# 01_-_Edge-connections.net
KiCad netlist of a schematic drawn in Altium Designer
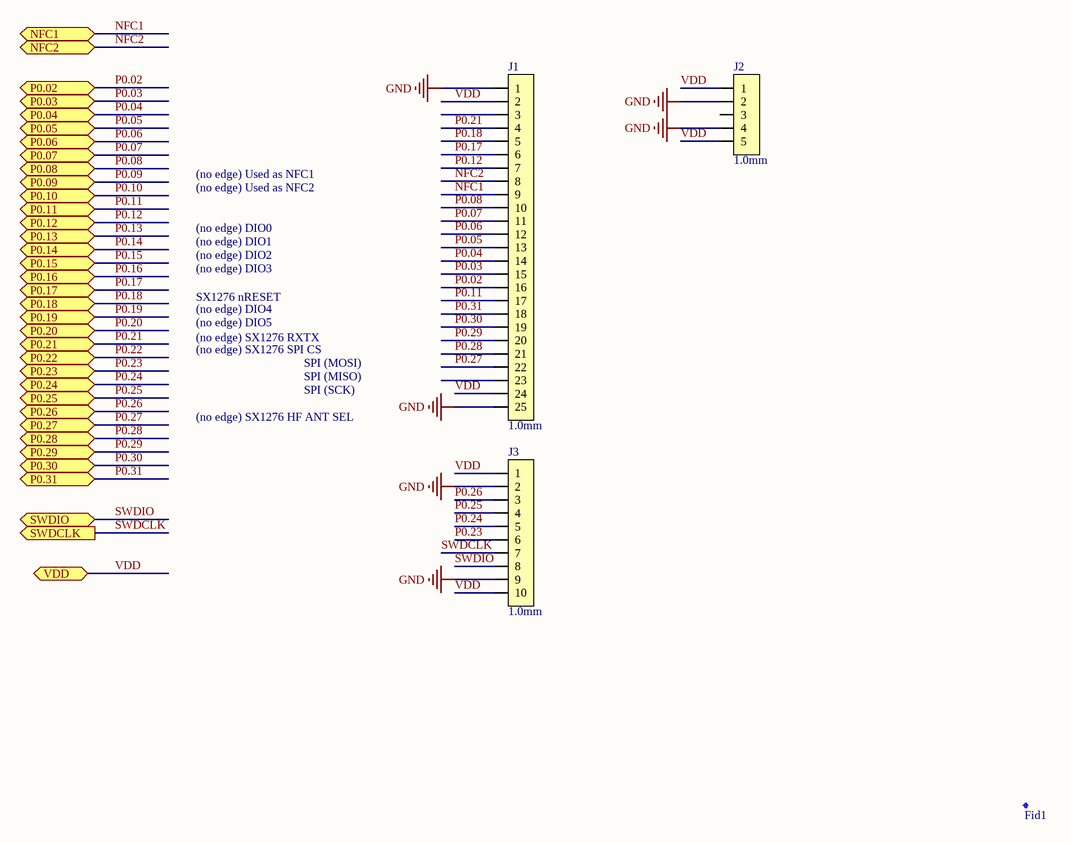
[diagram p0: [01] - Edge-connections.SchDoc]

(export (version "E")
  (design (tool "Eeschema 10.0.6"))
  (components
    (comp (ref "Fid1")
      (value "Fiducial mark")
      (footprint "Fiducial")
      (description "Fiducial Mark")
      (fields (field (name "PART NUMBER") "Fid-Mark") (field (name "PUBLISHER") "Nordic Semiconductor"))
      (libsource (lib "Skunkworks Library") (part "Fiducial"))
    )
    (comp (ref "J1")
      (value "1.0mm")
      (footprint "EDGE_MULTI_25")
      (description "Edge Connector, 25 pins, 1mm pitch")
      (libsource (lib "Skunkworks Library") (part "EDGE_MULTI_25_P_1mm"))
    )
    (comp (ref "J2")
      (value "1.0mm")
      (footprint "EDGE_MULTI_5")
      (description "Edge Connector, 5 pins, 1mm pitch")
      (libsource (lib "Skunkworks Library") (part "EDGE_MULTI_5_P_1mm"))
    )
    (comp (ref "J3")
      (value "1.0mm")
      (footprint "EDGE_MULTI_10")
      (description "Edge Connector, 10 pins, 1mm pitch")
      (libsource (lib "Skunkworks Library") (part "EDGE_MULTI_10_P_1mm"))
    )
    (comp (ref "LOGO1")
      (value "TELENOR_LOGO")
      (footprint "TELENOR_4mmx3.8mm")
      (libsource (lib "Skunkworks Library") (part "TELENOR_LOGO"))
    )
  )
  (nets
    (net (code "1") (name "/NFC1") (class "Default")
      (node (ref "J1") (pin "9") (pinfunction "9_9") (pintype "passive"))
    )
    (net (code "2") (name "/NFC2") (class "Default")
      (node (ref "J1") (pin "8") (pinfunction "8_8") (pintype "passive"))
    )
    (net (code "3") (name "/P0.02") (class "Default")
      (node (ref "J1") (pin "16") (pinfunction "16_16") (pintype "passive"))
    )
    (net (code "4") (name "/P0.03") (class "Default")
      (node (ref "J1") (pin "15") (pinfunction "15_15") (pintype "passive"))
    )
    (net (code "5") (name "/P0.04") (class "Default")
      (node (ref "J1") (pin "14") (pinfunction "14_14") (pintype "passive"))
    )
    (net (code "6") (name "/P0.05") (class "Default")
      (node (ref "J1") (pin "13") (pinfunction "13_13") (pintype "passive"))
    )
    (net (code "7") (name "/P0.06") (class "Default")
      (node (ref "J1") (pin "12") (pinfunction "12_12") (pintype "passive"))
    )
    (net (code "8") (name "/P0.07") (class "Default")
      (node (ref "J1") (pin "11") (pinfunction "11_11") (pintype "passive"))
    )
    (net (code "9") (name "/P0.08") (class "Default")
      (node (ref "J1") (pin "10") (pinfunction "10_10") (pintype "passive"))
    )
    (net (code "12") (name "/P0.11") (class "Default")
      (node (ref "J1") (pin "17") (pinfunction "17_17") (pintype "passive"))
    )
    (net (code "13") (name "/P0.12") (class "Default")
      (node (ref "J1") (pin "7") (pinfunction "7_7") (pintype "passive"))
    )
    (net (code "18") (name "/P0.17") (class "Default")
      (node (ref "J1") (pin "6") (pinfunction "6_6") (pintype "passive"))
    )
    (net (code "19") (name "/P0.18") (class "Default")
      (node (ref "J1") (pin "5") (pinfunction "5_5") (pintype "passive"))
    )
    (net (code "22") (name "/P0.21") (class "Default")
      (node (ref "J1") (pin "4") (pinfunction "4_4") (pintype "passive"))
    )
    (net (code "24") (name "/P0.23") (class "Default")
      (node (ref "J3") (pin "6") (pinfunction "6_6") (pintype "passive"))
    )
    (net (code "25") (name "/P0.24") (class "Default")
      (node (ref "J3") (pin "5") (pinfunction "5_5") (pintype "passive"))
    )
    (net (code "26") (name "/P0.25") (class "Default")
      (node (ref "J3") (pin "4") (pinfunction "4_4") (pintype "passive"))
    )
    (net (code "27") (name "/P0.26") (class "Default")
      (node (ref "J3") (pin "3") (pinfunction "3_3") (pintype "passive"))
    )
    (net (code "28") (name "/P0.27") (class "Default")
      (node (ref "J1") (pin "22") (pinfunction "22_22") (pintype "passive"))
    )
    (net (code "29") (name "/P0.28") (class "Default")
      (node (ref "J1") (pin "21") (pinfunction "21_21") (pintype "passive"))
    )
    (net (code "30") (name "/P0.29") (class "Default")
      (node (ref "J1") (pin "20") (pinfunction "20_20") (pintype "passive"))
    )
    (net (code "31") (name "/P0.30") (class "Default")
      (node (ref "J1") (pin "19") (pinfunction "19_19") (pintype "passive"))
    )
    (net (code "32") (name "/P0.31") (class "Default")
      (node (ref "J1") (pin "18") (pinfunction "18_18") (pintype "passive"))
    )
    (net (code "33") (name "/SWDCLK") (class "Default")
      (node (ref "J3") (pin "7") (pinfunction "7_7") (pintype "passive"))
    )
    (net (code "34") (name "/SWDIO") (class "Default")
      (node (ref "J3") (pin "8") (pinfunction "8_8") (pintype "passive"))
    )
    (net (code "35") (name "/VDD") (class "Default")
      (node (ref "J1") (pin "2") (pinfunction "2_2") (pintype "passive"))
      (node (ref "J1") (pin "24") (pinfunction "24_24") (pintype "passive"))
      (node (ref "J2") (pin "1") (pinfunction "1_1") (pintype "passive"))
      (node (ref "J2") (pin "5") (pinfunction "5_5") (pintype "passive"))
      (node (ref "J3") (pin "1") (pinfunction "1_1") (pintype "passive"))
      (node (ref "J3") (pin "10") (pinfunction "10_10") (pintype "passive"))
    )
    (net (code "36") (name "GND") (class "Default")
      (node (ref "J1") (pin "1") (pinfunction "1_1") (pintype "passive"))
      (node (ref "J1") (pin "25") (pinfunction "25_25") (pintype "passive"))
      (node (ref "J2") (pin "2") (pinfunction "2_2") (pintype "passive"))
      (node (ref "J2") (pin "4") (pinfunction "4_4") (pintype "passive"))
      (node (ref "J3") (pin "2") (pinfunction "2_2") (pintype "passive"))
      (node (ref "J3") (pin "9") (pinfunction "9_9") (pintype "passive"))
    )
    (net (code "37") (name "unconnected-(J1-Pad3)") (class "Default")
      (node (ref "J1") (pin "3") (pinfunction "3_3") (pintype "passive"))
    )
    (net (code "38") (name "unconnected-(J1-Pad23)") (class "Default")
      (node (ref "J1") (pin "23") (pinfunction "23_23") (pintype "passive"))
    )
    (net (code "39") (name "unconnected-(J2-Pad3)") (class "Default")
      (node (ref "J2") (pin "3") (pinfunction "3_3") (pintype "passive"))
    )
  )
)
